# lpc812_breakout.net
KiCad netlist of a schematic drawn in EAGLE
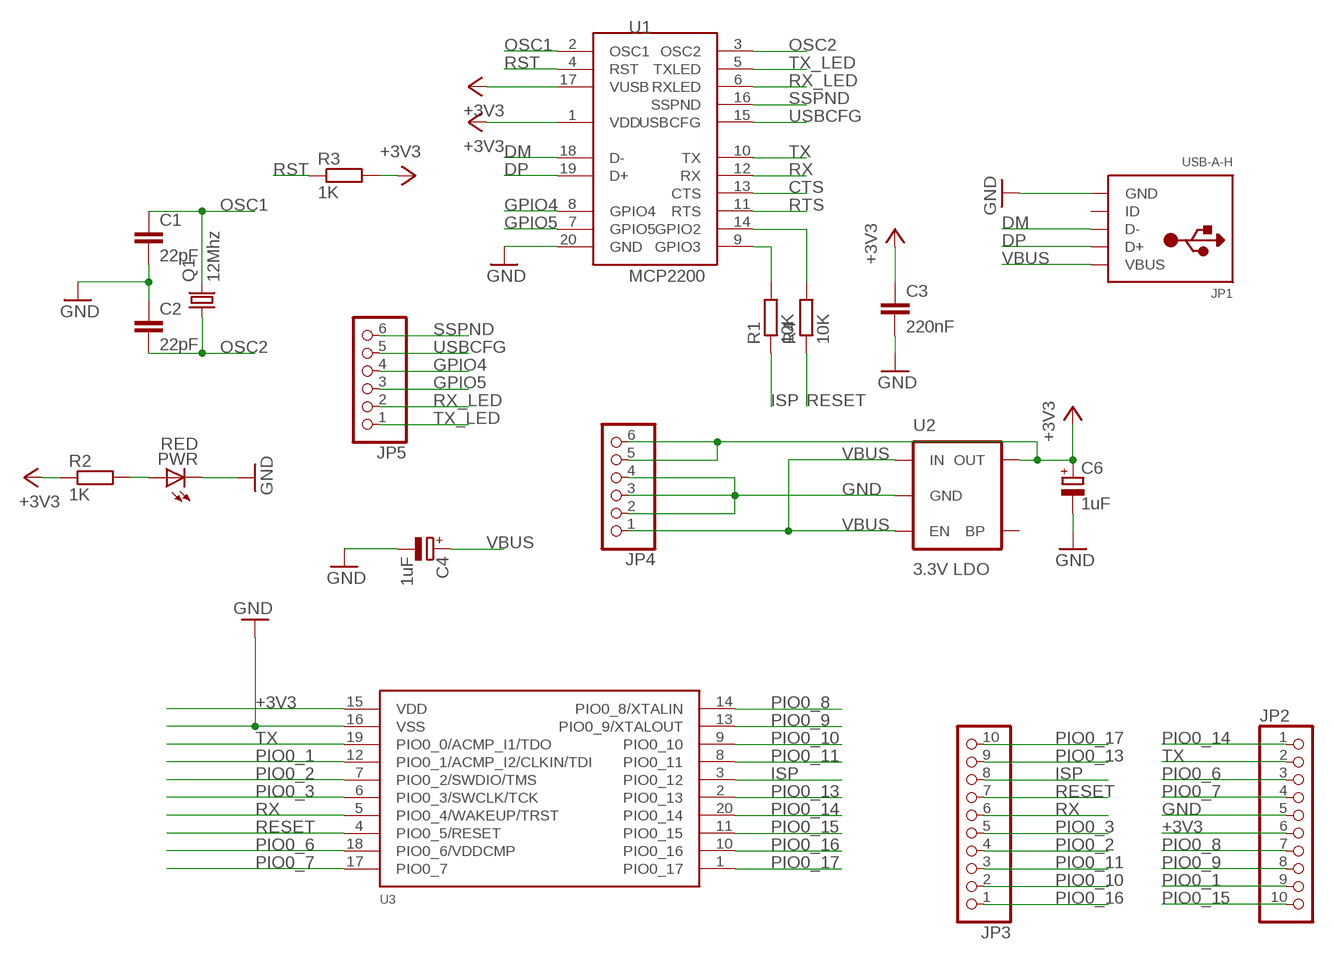
[diagram p0: schematic, sheet 1]

(export (version "E")
  (design (tool "Eeschema 10.0.6"))
  (components
    (comp (ref "C1")
      (value "22pF")
      (footprint "eagle-import:C1206")
      (libsource (lib "eagle-import") (part "C-EUC1206"))
    )
    (comp (ref "C2")
      (value "22pF")
      (footprint "eagle-import:C1206")
      (libsource (lib "eagle-import") (part "C-EUC1206"))
    )
    (comp (ref "C3")
      (value "220nF")
      (footprint "eagle-import:C1206")
      (libsource (lib "eagle-import") (part "C-EUC1206"))
    )
    (comp (ref "C4")
      (value "1uF")
      (footprint "eagle-import:A_3216-18R")
      (libsource (lib "eagle-import") (part "CPOL-EUA/3216-18R"))
    )
    (comp (ref "C6")
      (value "1uF")
      (footprint "eagle-import:A_3216-18R")
      (libsource (lib "eagle-import") (part "CPOL-EUA/3216-18R"))
    )
    (comp (ref "JP1")
      (value "USB-A-H")
      (footprint "eagle-import:USB-MINIB-THM-MOLEX")
      (libsource (lib "eagle-import") (part "USBMOLEX"))
    )
    (comp (ref "JP2")
      (value "HEADER-1X10ROUND")
      (footprint "eagle-import:1X10_ROUND")
      (libsource (lib "eagle-import") (part "HEADER-1X10ROUND"))
    )
    (comp (ref "JP3")
      (value "HEADER-1X10ROUND")
      (footprint "eagle-import:1X10_ROUND")
      (libsource (lib "eagle-import") (part "HEADER-1X10ROUND"))
    )
    (comp (ref "JP4")
      (value "HEADER-1X6ROUND")
      (footprint "eagle-import:1X06_ROUND")
      (libsource (lib "eagle-import") (part "HEADER-1X6ROUND"))
    )
    (comp (ref "JP5")
      (value "HEADER-1X6ROUND")
      (footprint "eagle-import:1X06_ROUND")
      (libsource (lib "eagle-import") (part "HEADER-1X6ROUND"))
    )
    (comp (ref "PWR")
      (value "RED")
      (footprint "eagle-import:1206")
      (libsource (lib "eagle-import") (part "LEDSMT1206"))
    )
    (comp (ref "Q1")
      (value "12Mhz")
      (footprint "eagle-import:HC49_S")
      (libsource (lib "eagle-import") (part "CRYSTALHC49S"))
    )
    (comp (ref "R1")
      (value "10K")
      (footprint "eagle-import:R1206")
      (libsource (lib "eagle-import") (part "R-EU_R1206"))
    )
    (comp (ref "R2")
      (value "1K")
      (footprint "eagle-import:R1206")
      (libsource (lib "eagle-import") (part "R-EU_R1206"))
    )
    (comp (ref "R3")
      (value "1K")
      (footprint "eagle-import:R1206")
      (libsource (lib "eagle-import") (part "R-EU_R1206"))
    )
    (comp (ref "R4")
      (value "10K")
      (footprint "eagle-import:R1206")
      (libsource (lib "eagle-import") (part "R-EU_R1206"))
    )
    (comp (ref "U1")
      (value "MCP2200")
      (footprint "eagle-import:SSOP20")
      (libsource (lib "eagle-import") (part "MCP2200"))
    )
    (comp (ref "U2")
      (value "3.3V LDO")
      (footprint "eagle-import:SOT23-5")
      (libsource (lib "eagle-import") (part "V_REG_LDOSMD"))
    )
    (comp (ref "U3")
      (value "LPC812M101JDH20")
      (footprint "eagle-import:TSSOP20")
      (libsource (lib "eagle-import") (part "LPC812M101JDH20"))
    )
  )
  (nets
    (net (code "1") (name "+3V3") (class "Default")
      (node (ref "C3") (pin "1") (pinfunction "1_1") (pintype "passive"))
      (node (ref "C6") (pin "+") (pinfunction "+_+") (pintype "passive"))
      (node (ref "JP2") (pin "6") (pinfunction "6_6") (pintype "passive"))
      (node (ref "JP4") (pin "5") (pinfunction "5_5") (pintype "passive"))
      (node (ref "JP4") (pin "6") (pinfunction "6_6") (pintype "passive"))
      (node (ref "R2") (pin "1") (pinfunction "1_1") (pintype "passive"))
      (node (ref "R3") (pin "2") (pinfunction "2_2") (pintype "passive"))
      (node (ref "U1") (pin "1") (pinfunction "VDD_1") (pintype "bidirectional"))
      (node (ref "U1") (pin "17") (pinfunction "VUSB_17") (pintype "bidirectional"))
      (node (ref "U2") (pin "5") (pinfunction "OUT_5") (pintype "passive"))
      (node (ref "U3") (pin "15") (pinfunction "VDD_15") (pintype "bidirectional"))
    )
    (net (code "2") (name "/CTS") (class "Default")
      (node (ref "U1") (pin "13") (pinfunction "CTS_13") (pintype "bidirectional"))
    )
    (net (code "3") (name "/DM") (class "Default")
      (node (ref "JP1") (pin "D-") (pinfunction "D-_D-") (pintype "bidirectional"))
      (node (ref "U1") (pin "18") (pinfunction "D-_18") (pintype "bidirectional"))
    )
    (net (code "4") (name "/DP") (class "Default")
      (node (ref "JP1") (pin "D+") (pinfunction "D+_D+") (pintype "bidirectional"))
      (node (ref "U1") (pin "19") (pinfunction "D+_19") (pintype "bidirectional"))
    )
    (net (code "5") (name "/GPIO4") (class "Default")
      (node (ref "JP5") (pin "4") (pinfunction "4_4") (pintype "passive"))
      (node (ref "U1") (pin "8") (pinfunction "GPIO4_8") (pintype "bidirectional"))
    )
    (net (code "6") (name "/GPIO5") (class "Default")
      (node (ref "JP5") (pin "3") (pinfunction "3_3") (pintype "passive"))
      (node (ref "U1") (pin "7") (pinfunction "GPIO5_7") (pintype "bidirectional"))
    )
    (net (code "7") (name "/ISP") (class "Default")
      (node (ref "JP3") (pin "8") (pinfunction "8_8") (pintype "passive"))
      (node (ref "R1") (pin "1") (pinfunction "1_1") (pintype "passive"))
      (node (ref "U3") (pin "3") (pinfunction "PIO0_12_3") (pintype "bidirectional"))
    )
    (net (code "8") (name "/OSC1") (class "Default")
      (node (ref "C1") (pin "1") (pinfunction "1_1") (pintype "passive"))
      (node (ref "Q1") (pin "2") (pinfunction "2_2") (pintype "passive"))
      (node (ref "U1") (pin "2") (pinfunction "OSC1_2") (pintype "bidirectional"))
    )
    (net (code "9") (name "/OSC2") (class "Default")
      (node (ref "C2") (pin "2") (pinfunction "2_2") (pintype "passive"))
      (node (ref "Q1") (pin "1") (pinfunction "1_1") (pintype "passive"))
      (node (ref "U1") (pin "3") (pinfunction "OSC2_3") (pintype "bidirectional"))
    )
    (net (code "10") (name "/PIO0_1") (class "Default")
      (node (ref "JP2") (pin "9") (pinfunction "9_9") (pintype "passive"))
      (node (ref "U3") (pin "12") (pinfunction "PIO0_1/ACMP_I2/CLKIN/TDI_12") (pintype "bidirectional"))
    )
    (net (code "11") (name "/PIO0_2") (class "Default")
      (node (ref "JP3") (pin "4") (pinfunction "4_4") (pintype "passive"))
      (node (ref "U3") (pin "7") (pinfunction "PIO0_2/SWDIO/TMS_7") (pintype "bidirectional"))
    )
    (net (code "12") (name "/PIO0_3") (class "Default")
      (node (ref "JP3") (pin "5") (pinfunction "5_5") (pintype "passive"))
      (node (ref "U3") (pin "6") (pinfunction "PIO0_3/SWCLK/TCK_6") (pintype "bidirectional"))
    )
    (net (code "13") (name "/PIO0_6") (class "Default")
      (node (ref "JP2") (pin "3") (pinfunction "3_3") (pintype "passive"))
      (node (ref "U3") (pin "18") (pinfunction "PIO0_6/VDDCMP_18") (pintype "bidirectional"))
    )
    (net (code "14") (name "/PIO0_7") (class "Default")
      (node (ref "JP2") (pin "4") (pinfunction "4_4") (pintype "passive"))
      (node (ref "U3") (pin "17") (pinfunction "PIO0_7_17") (pintype "bidirectional"))
    )
    (net (code "15") (name "/PIO0_8") (class "Default")
      (node (ref "JP2") (pin "7") (pinfunction "7_7") (pintype "passive"))
      (node (ref "U3") (pin "14") (pinfunction "PIO0_8/XTALIN_14") (pintype "bidirectional"))
    )
    (net (code "16") (name "/PIO0_9") (class "Default")
      (node (ref "JP2") (pin "8") (pinfunction "8_8") (pintype "passive"))
      (node (ref "U3") (pin "13") (pinfunction "PIO0_9/XTALOUT_13") (pintype "bidirectional"))
    )
    (net (code "17") (name "/PIO0_10") (class "Default")
      (node (ref "JP3") (pin "2") (pinfunction "2_2") (pintype "passive"))
      (node (ref "U3") (pin "9") (pinfunction "PIO0_10_9") (pintype "bidirectional"))
    )
    (net (code "18") (name "/PIO0_11") (class "Default")
      (node (ref "JP3") (pin "3") (pinfunction "3_3") (pintype "passive"))
      (node (ref "U3") (pin "8") (pinfunction "PIO0_11_8") (pintype "bidirectional"))
    )
    (net (code "19") (name "/PIO0_13") (class "Default")
      (node (ref "JP3") (pin "9") (pinfunction "9_9") (pintype "passive"))
      (node (ref "U3") (pin "2") (pinfunction "PIO0_13_2") (pintype "bidirectional"))
    )
    (net (code "20") (name "/PIO0_14") (class "Default")
      (node (ref "JP2") (pin "1") (pinfunction "1_1") (pintype "passive"))
      (node (ref "U3") (pin "20") (pinfunction "PIO0_14_20") (pintype "bidirectional"))
    )
    (net (code "21") (name "/PIO0_15") (class "Default")
      (node (ref "JP2") (pin "10") (pinfunction "10_10") (pintype "passive"))
      (node (ref "U3") (pin "11") (pinfunction "PIO0_15_11") (pintype "bidirectional"))
    )
    (net (code "22") (name "/PIO0_16") (class "Default")
      (node (ref "JP3") (pin "1") (pinfunction "1_1") (pintype "passive"))
      (node (ref "U3") (pin "10") (pinfunction "PIO0_16_10") (pintype "bidirectional"))
    )
    (net (code "23") (name "/PIO0_17") (class "Default")
      (node (ref "JP3") (pin "10") (pinfunction "10_10") (pintype "passive"))
      (node (ref "U3") (pin "1") (pinfunction "PIO0_17_1") (pintype "bidirectional"))
    )
    (net (code "24") (name "/RESET") (class "Default")
      (node (ref "JP3") (pin "7") (pinfunction "7_7") (pintype "passive"))
      (node (ref "R4") (pin "1") (pinfunction "1_1") (pintype "passive"))
      (node (ref "U3") (pin "4") (pinfunction "PIO0_5/RESET_4") (pintype "bidirectional"))
    )
    (net (code "25") (name "/RST") (class "Default")
      (node (ref "R3") (pin "1") (pinfunction "1_1") (pintype "passive"))
      (node (ref "U1") (pin "4") (pinfunction "RST_4") (pintype "bidirectional"))
    )
    (net (code "26") (name "/RTS") (class "Default")
      (node (ref "U1") (pin "11") (pinfunction "RTS_11") (pintype "bidirectional"))
    )
    (net (code "27") (name "/RX") (class "Default")
      (node (ref "JP3") (pin "6") (pinfunction "6_6") (pintype "passive"))
      (node (ref "U1") (pin "12") (pinfunction "RX_12") (pintype "bidirectional"))
      (node (ref "U3") (pin "5") (pinfunction "PIO0_4/WAKEUP/TRST_5") (pintype "bidirectional"))
    )
    (net (code "28") (name "/RX_LED") (class "Default")
      (node (ref "JP5") (pin "2") (pinfunction "2_2") (pintype "passive"))
      (node (ref "U1") (pin "6") (pinfunction "RXLED_6") (pintype "bidirectional"))
    )
    (net (code "29") (name "/SSPND") (class "Default")
      (node (ref "JP5") (pin "6") (pinfunction "6_6") (pintype "passive"))
      (node (ref "U1") (pin "16") (pinfunction "SSPND_16") (pintype "bidirectional"))
    )
    (net (code "30") (name "/TX") (class "Default")
      (node (ref "JP2") (pin "2") (pinfunction "2_2") (pintype "passive"))
      (node (ref "U1") (pin "10") (pinfunction "TX_10") (pintype "bidirectional"))
      (node (ref "U3") (pin "19") (pinfunction "PIO0_0/ACMP_I1/TDO_19") (pintype "bidirectional"))
    )
    (net (code "31") (name "/TX_LED") (class "Default")
      (node (ref "JP5") (pin "1") (pinfunction "1_1") (pintype "passive"))
      (node (ref "U1") (pin "5") (pinfunction "TXLED_5") (pintype "bidirectional"))
    )
    (net (code "32") (name "/USBCFG") (class "Default")
      (node (ref "JP5") (pin "5") (pinfunction "5_5") (pintype "passive"))
      (node (ref "U1") (pin "15") (pinfunction "USBCFG_15") (pintype "bidirectional"))
    )
    (net (code "33") (name "/VBUS") (class "Default")
      (node (ref "C4") (pin "+") (pinfunction "+_+") (pintype "passive"))
      (node (ref "JP1") (pin "VBUS") (pinfunction "VBUS_VBUS") (pintype "power_in"))
      (node (ref "JP4") (pin "1") (pinfunction "1_1") (pintype "passive"))
      (node (ref "U2") (pin "1") (pinfunction "IN_1") (pintype "input"))
      (node (ref "U2") (pin "3") (pinfunction "EN_3") (pintype "input"))
    )
    (net (code "34") (name "GND") (class "Default")
      (node (ref "C1") (pin "2") (pinfunction "2_2") (pintype "passive"))
      (node (ref "C2") (pin "1") (pinfunction "1_1") (pintype "passive"))
      (node (ref "C3") (pin "2") (pinfunction "2_2") (pintype "passive"))
      (node (ref "C4") (pin "-") (pinfunction "-_-") (pintype "passive"))
      (node (ref "C6") (pin "-") (pinfunction "-_-") (pintype "passive"))
      (node (ref "JP1") (pin "GND") (pinfunction "GND_GND") (pintype "power_in"))
      (node (ref "JP2") (pin "5") (pinfunction "5_5") (pintype "passive"))
      (node (ref "JP4") (pin "2") (pinfunction "2_2") (pintype "passive"))
      (node (ref "JP4") (pin "3") (pinfunction "3_3") (pintype "passive"))
      (node (ref "JP4") (pin "4") (pinfunction "4_4") (pintype "passive"))
      (node (ref "PWR") (pin "C") (pinfunction "C_C") (pintype "passive"))
      (node (ref "U1") (pin "20") (pinfunction "GND_20") (pintype "bidirectional"))
      (node (ref "U2") (pin "2") (pinfunction "GND_2") (pintype "input"))
      (node (ref "U3") (pin "16") (pinfunction "VSS_16") (pintype "bidirectional"))
    )
    (net (code "35") (name "Net-(PWR-PadA)") (class "Default")
      (node (ref "PWR") (pin "A") (pinfunction "A_A") (pintype "passive"))
      (node (ref "R2") (pin "2") (pinfunction "2_2") (pintype "passive"))
    )
    (net (code "36") (name "Net-(U1-GPIO2)") (class "Default")
      (node (ref "R4") (pin "2") (pinfunction "2_2") (pintype "passive"))
      (node (ref "U1") (pin "14") (pinfunction "GPIO2_14") (pintype "bidirectional"))
    )
    (net (code "37") (name "Net-(U1-GPIO3)") (class "Default")
      (node (ref "R1") (pin "2") (pinfunction "2_2") (pintype "passive"))
      (node (ref "U1") (pin "9") (pinfunction "GPIO3_9") (pintype "bidirectional"))
    )
    (net (code "38") (name "unconnected-(JP1-PadID)") (class "Default")
      (node (ref "JP1") (pin "ID") (pinfunction "ID_ID") (pintype "bidirectional"))
    )
    (net (code "39") (name "unconnected-(U2-BP-Pad4)") (class "Default")
      (node (ref "U2") (pin "4") (pinfunction "BP_4") (pintype "input"))
    )
  )
)
